# pcmcia.net
KiCad netlist of a schematic drawn in Altium Designer
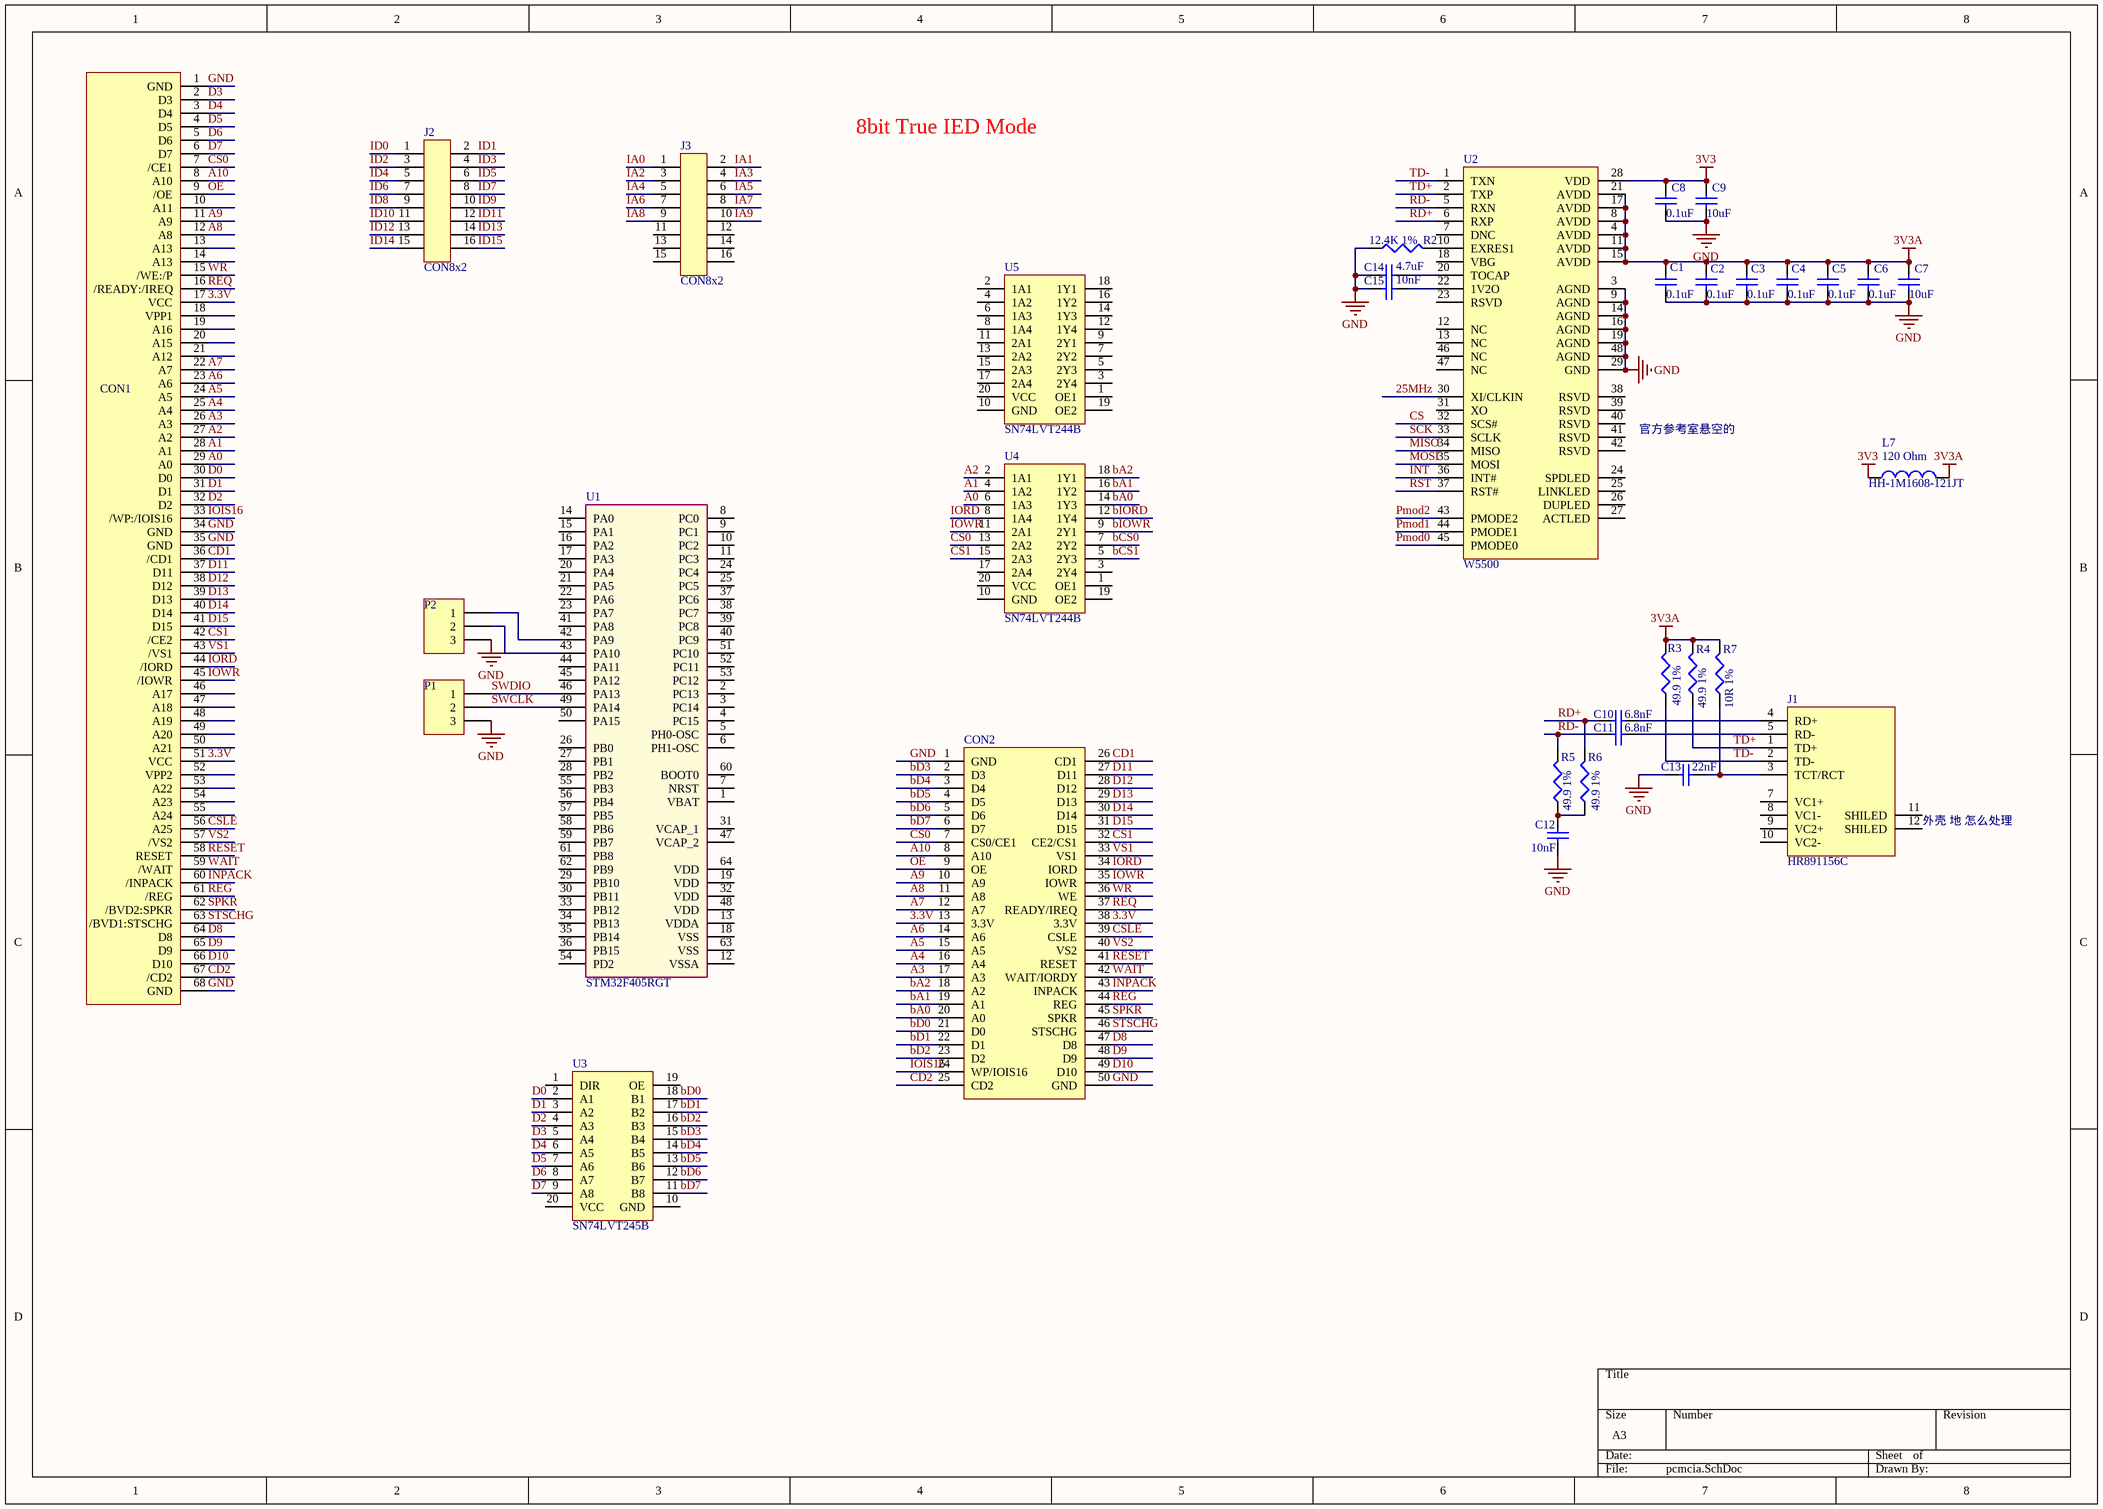
[diagram p0: pcmcia.SchDoc]

(export (version "E")
  (design (tool "Eeschema 10.0.6"))
  (components
    (comp (ref "C1")
      (value "0.1uF")
      (footprint "0603_C")
      (fields (field (name "PUBLISHER") "Altium Limited"))
      (libsource (lib "misc") (part "Cap"))
    )
    (comp (ref "C2")
      (value "0.1uF")
      (footprint "0603_C")
      (fields (field (name "PUBLISHER") "Altium Limited"))
      (libsource (lib "misc") (part "Cap"))
    )
    (comp (ref "C3")
      (value "0.1uF")
      (footprint "0603_C")
      (fields (field (name "PUBLISHER") "Altium Limited"))
      (libsource (lib "misc") (part "Cap"))
    )
    (comp (ref "C4")
      (value "0.1uF")
      (footprint "0603_C")
      (fields (field (name "PUBLISHER") "Altium Limited"))
      (libsource (lib "misc") (part "Cap"))
    )
    (comp (ref "C5")
      (value "0.1uF")
      (footprint "0603_C")
      (fields (field (name "PUBLISHER") "Altium Limited"))
      (libsource (lib "misc") (part "Cap"))
    )
    (comp (ref "C6")
      (value "0.1uF")
      (footprint "0603_C")
      (fields (field (name "PUBLISHER") "Altium Limited"))
      (libsource (lib "misc") (part "Cap"))
    )
    (comp (ref "C7")
      (value "10uF")
      (footprint "0603_C")
      (fields (field (name "PUBLISHER") "Altium Limited"))
      (libsource (lib "misc") (part "Cap"))
    )
    (comp (ref "C8")
      (value "0.1uF")
      (footprint "C0603")
      (fields (field (name "PUBLISHER") "Altium Limited"))
      (libsource (lib "misc") (part "Cap"))
    )
    (comp (ref "C9")
      (value "10uF")
      (footprint "C0603")
      (fields (field (name "PUBLISHER") "Altium Limited"))
      (libsource (lib "misc") (part "Cap"))
    )
    (comp (ref "C10")
      (value "6.8nF")
      (footprint "0603_C")
      (fields (field (name "PUBLISHER") "Altium Limited"))
      (libsource (lib "misc") (part "Cap"))
    )
    (comp (ref "C11")
      (value "6.8nF")
      (footprint "0603_C")
      (fields (field (name "PUBLISHER") "Altium Limited"))
      (libsource (lib "misc") (part "Cap"))
    )
    (comp (ref "C12")
      (value "10nF")
      (footprint "0603_C")
      (fields (field (name "PUBLISHER") "Altium Limited"))
      (libsource (lib "misc") (part "Cap"))
    )
    (comp (ref "C13")
      (value "22nF")
      (footprint "0603_C")
      (fields (field (name "PUBLISHER") "Altium Limited"))
      (libsource (lib "misc") (part "Cap"))
    )
    (comp (ref "C14")
      (value "4.7uF")
      (footprint "0603_C")
      (fields (field (name "PUBLISHER") "Altium Limited"))
      (libsource (lib "misc") (part "Cap"))
    )
    (comp (ref "C15")
      (value "10nF")
      (footprint "0603_C")
      (fields (field (name "PUBLISHER") "Altium Limited"))
      (libsource (lib "misc") (part "Cap"))
    )
    (comp (ref "CON1")
      (value "Ultrasonic")
      (footprint "PCMCIA_68pin_F")
      (libsource (lib "pcmcia") (part "Ultrasonic"))
    )
    (comp (ref "CON2") (value "AT89S52_1") (footprint "DIP40") (libsource (lib "pcmcia") (part "AT89S52_1")))
    (comp (ref "J1")
      (value "HR891156C")
      (footprint "HR891156C")
      (description "with POE")
      (libsource (lib "misc1") (part "HR891156C"))
    )
    (comp (ref "J2") (value "CON8x2") (footprint "CON8x2") (libsource (lib "misc") (part "CON8x2")))
    (comp (ref "J3") (value "CON8x2") (footprint "CON8x2") (libsource (lib "misc") (part "CON8x2")))
    (comp (ref "L7")
      (value "HH-1M1608-121JT")
      (footprint "L0805")
      (fields (field (name "ALTIUM_UNNAMED_1") "120 Ohm") (field (name "PUBLISHER") "Altium Limited"))
      (libsource (lib "misc") (part "Ind"))
    )
    (comp (ref "P1")
      (value "~")
      (footprint "CON3-SMT")
      (description "Header, 3-Pin")
      (fields (field (name "PUBLISHER") "Altium Limited"))
      (libsource (lib "Miscellaneous Connectors") (part "Header 3"))
    )
    (comp (ref "P2")
      (value "~")
      (footprint "CON3-SMT")
      (description "Header, 3-Pin")
      (fields (field (name "PUBLISHER") "Altium Limited"))
      (libsource (lib "Miscellaneous Connectors") (part "Header 3"))
    )
    (comp (ref "R2")
      (value "12.4K 1%")
      (footprint "0603_R")
      (fields (field (name "PUBLISHER") "Altium Limited"))
      (libsource (lib "misc") (part "Res"))
    )
    (comp (ref "R3")
      (value "49.9 1%")
      (footprint "0603_R")
      (fields (field (name "PUBLISHER") "Altium Limited"))
      (libsource (lib "misc") (part "Res"))
    )
    (comp (ref "R4")
      (value "49.9 1%")
      (footprint "0603_R")
      (fields (field (name "PUBLISHER") "Altium Limited"))
      (libsource (lib "misc") (part "Res"))
    )
    (comp (ref "R5")
      (value "49.9 1%")
      (footprint "0603_R")
      (fields (field (name "PUBLISHER") "Altium Limited"))
      (libsource (lib "misc") (part "Res"))
    )
    (comp (ref "R6")
      (value "49.9 1%")
      (footprint "0603_R")
      (fields (field (name "PUBLISHER") "Altium Limited"))
      (libsource (lib "misc") (part "Res"))
    )
    (comp (ref "R7")
      (value "10R 1%")
      (footprint "0603_R")
      (fields (field (name "PUBLISHER") "Altium Limited"))
      (libsource (lib "misc") (part "Res"))
    )
    (comp (ref "U1")
      (value "STM32F405RGT")
      (footprint "LQFP64-10x10")
      (libsource (lib "MCU") (part "STM32F405RGT"))
    )
    (comp (ref "U2") (value "W5500") (footprint "LQFP48-7x7") (libsource (lib "misc1") (part "W5500")))
    (comp (ref "U3") (value "SN74LVT245B") (libsource (lib "misc1") (part "SN74LVT245B")))
    (comp (ref "U4") (value "SN74LVT244B") (libsource (lib "misc1") (part "SN74LVT244B")))
    (comp (ref "U5") (value "SN74LVT244B") (libsource (lib "misc1") (part "SN74LVT244B")))
  )
  (nets
    (net (code "1") (name "/3.3V") (class "Default")
      (node (ref "CON1") (pin "17") (pinfunction "VCC_17") (pintype "passive"))
      (node (ref "CON1") (pin "51") (pinfunction "VCC_51") (pintype "passive"))
      (node (ref "CON2") (pin "13") (pinfunction "3.3V_13") (pintype "passive"))
      (node (ref "CON2") (pin "38") (pinfunction "3.3V_38") (pintype "passive"))
    )
    (net (code "2") (name "/25MHz") (class "Default")
      (node (ref "U2") (pin "30") (pinfunction "XI/CLKIN_30") (pintype "passive"))
    )
    (net (code "3") (name "/A0") (class "Default")
      (node (ref "CON1") (pin "29") (pinfunction "A0_29") (pintype "passive"))
      (node (ref "U4") (pin "6") (pinfunction "1A3_6") (pintype "passive"))
    )
    (net (code "4") (name "/A1") (class "Default")
      (node (ref "CON1") (pin "28") (pinfunction "A1_28") (pintype "passive"))
      (node (ref "U4") (pin "4") (pinfunction "1A2_4") (pintype "passive"))
    )
    (net (code "5") (name "/A2") (class "Default")
      (node (ref "CON1") (pin "27") (pinfunction "A2_27") (pintype "passive"))
      (node (ref "U4") (pin "2") (pinfunction "1A1_2") (pintype "passive"))
    )
    (net (code "6") (name "/A3") (class "Default")
      (node (ref "CON1") (pin "26") (pinfunction "A3_26") (pintype "passive"))
      (node (ref "CON2") (pin "17") (pinfunction "A3_17") (pintype "passive"))
    )
    (net (code "7") (name "/A4") (class "Default")
      (node (ref "CON1") (pin "25") (pinfunction "A4_25") (pintype "passive"))
      (node (ref "CON2") (pin "16") (pinfunction "A4_16") (pintype "passive"))
    )
    (net (code "8") (name "/A5") (class "Default")
      (node (ref "CON1") (pin "24") (pinfunction "A5_24") (pintype "passive"))
      (node (ref "CON2") (pin "15") (pinfunction "A5_15") (pintype "passive"))
    )
    (net (code "9") (name "/A6") (class "Default")
      (node (ref "CON1") (pin "23") (pinfunction "A6_23") (pintype "passive"))
      (node (ref "CON2") (pin "14") (pinfunction "A6_14") (pintype "passive"))
    )
    (net (code "10") (name "/A7") (class "Default")
      (node (ref "CON1") (pin "22") (pinfunction "A7_22") (pintype "passive"))
      (node (ref "CON2") (pin "12") (pinfunction "A7_12") (pintype "passive"))
    )
    (net (code "11") (name "/A8") (class "Default")
      (node (ref "CON1") (pin "12") (pinfunction "A8_12") (pintype "passive"))
      (node (ref "CON2") (pin "11") (pinfunction "A8_11") (pintype "passive"))
    )
    (net (code "12") (name "/A9") (class "Default")
      (node (ref "CON1") (pin "11") (pinfunction "A9_11") (pintype "passive"))
      (node (ref "CON2") (pin "10") (pinfunction "A9_10") (pintype "passive"))
    )
    (net (code "13") (name "/A10") (class "Default")
      (node (ref "CON1") (pin "8") (pinfunction "A10_8") (pintype "passive"))
      (node (ref "CON2") (pin "8") (pinfunction "A10_8") (pintype "passive"))
    )
    (net (code "14") (name "/CD1") (class "Default")
      (node (ref "CON1") (pin "36") (pinfunction "/CD1_36") (pintype "passive"))
      (node (ref "CON2") (pin "26") (pinfunction "CD1_26") (pintype "passive"))
    )
    (net (code "15") (name "/CD2") (class "Default")
      (node (ref "CON1") (pin "67") (pinfunction "/CD2_67") (pintype "passive"))
      (node (ref "CON2") (pin "25") (pinfunction "CD2_25") (pintype "passive"))
    )
    (net (code "16") (name "/CS") (class "Default")
      (node (ref "U2") (pin "32") (pinfunction "SCS#_32") (pintype "passive"))
    )
    (net (code "17") (name "/CS0") (class "Default")
      (node (ref "CON1") (pin "7") (pinfunction "/CE1_7") (pintype "passive"))
      (node (ref "CON2") (pin "7") (pinfunction "CS0/CE1_7") (pintype "passive"))
      (node (ref "U4") (pin "13") (pinfunction "2A2_13") (pintype "passive"))
    )
    (net (code "18") (name "/CS1") (class "Default")
      (node (ref "CON1") (pin "42") (pinfunction "/CE2_42") (pintype "passive"))
      (node (ref "CON2") (pin "32") (pinfunction "CE2/CS1_32") (pintype "passive"))
      (node (ref "U4") (pin "15") (pinfunction "2A3_15") (pintype "passive"))
    )
    (net (code "19") (name "/CSLE") (class "Default")
      (node (ref "CON1") (pin "56") (pinfunction "A25_56") (pintype "passive"))
      (node (ref "CON2") (pin "39") (pinfunction "CSLE_39") (pintype "passive"))
    )
    (net (code "20") (name "/D0") (class "Default")
      (node (ref "CON1") (pin "30") (pinfunction "D0_30") (pintype "passive"))
      (node (ref "U3") (pin "2") (pinfunction "A1_2") (pintype "passive"))
    )
    (net (code "21") (name "/D1") (class "Default")
      (node (ref "CON1") (pin "31") (pinfunction "D1_31") (pintype "passive"))
      (node (ref "U3") (pin "3") (pinfunction "A2_3") (pintype "passive"))
    )
    (net (code "22") (name "/D2") (class "Default")
      (node (ref "CON1") (pin "32") (pinfunction "D2_32") (pintype "passive"))
      (node (ref "U3") (pin "4") (pinfunction "A3_4") (pintype "passive"))
    )
    (net (code "23") (name "/D3") (class "Default")
      (node (ref "CON1") (pin "2") (pinfunction "D3_2") (pintype "passive"))
      (node (ref "U3") (pin "5") (pinfunction "A4_5") (pintype "passive"))
    )
    (net (code "24") (name "/D4") (class "Default")
      (node (ref "CON1") (pin "3") (pinfunction "D4_3") (pintype "passive"))
      (node (ref "U3") (pin "6") (pinfunction "A5_6") (pintype "passive"))
    )
    (net (code "25") (name "/D5") (class "Default")
      (node (ref "CON1") (pin "4") (pinfunction "D5_4") (pintype "passive"))
      (node (ref "U3") (pin "7") (pinfunction "A6_7") (pintype "passive"))
    )
    (net (code "26") (name "/D6") (class "Default")
      (node (ref "CON1") (pin "5") (pinfunction "D6_5") (pintype "passive"))
      (node (ref "U3") (pin "8") (pinfunction "A7_8") (pintype "passive"))
    )
    (net (code "27") (name "/D7") (class "Default")
      (node (ref "CON1") (pin "6") (pinfunction "D7_6") (pintype "passive"))
      (node (ref "U3") (pin "9") (pinfunction "A8_9") (pintype "passive"))
    )
    (net (code "28") (name "/D8") (class "Default")
      (node (ref "CON1") (pin "64") (pinfunction "D8_64") (pintype "passive"))
      (node (ref "CON2") (pin "47") (pinfunction "D8_47") (pintype "passive"))
    )
    (net (code "29") (name "/D9") (class "Default")
      (node (ref "CON1") (pin "65") (pinfunction "D9_65") (pintype "passive"))
      (node (ref "CON2") (pin "48") (pinfunction "D9_48") (pintype "passive"))
    )
    (net (code "30") (name "/D10") (class "Default")
      (node (ref "CON1") (pin "66") (pinfunction "D10_66") (pintype "passive"))
      (node (ref "CON2") (pin "49") (pinfunction "D10_49") (pintype "passive"))
    )
    (net (code "31") (name "/D11") (class "Default")
      (node (ref "CON1") (pin "37") (pinfunction "D11_37") (pintype "passive"))
      (node (ref "CON2") (pin "27") (pinfunction "D11_27") (pintype "passive"))
    )
    (net (code "32") (name "/D12") (class "Default")
      (node (ref "CON1") (pin "38") (pinfunction "D12_38") (pintype "passive"))
      (node (ref "CON2") (pin "28") (pinfunction "D12_28") (pintype "passive"))
    )
    (net (code "33") (name "/D13") (class "Default")
      (node (ref "CON1") (pin "39") (pinfunction "D13_39") (pintype "passive"))
      (node (ref "CON2") (pin "29") (pinfunction "D13_29") (pintype "passive"))
    )
    (net (code "34") (name "/D14") (class "Default")
      (node (ref "CON1") (pin "40") (pinfunction "D14_40") (pintype "passive"))
      (node (ref "CON2") (pin "30") (pinfunction "D14_30") (pintype "passive"))
    )
    (net (code "35") (name "/D15") (class "Default")
      (node (ref "CON1") (pin "41") (pinfunction "D15_41") (pintype "passive"))
      (node (ref "CON2") (pin "31") (pinfunction "D15_31") (pintype "passive"))
    )
    (net (code "36") (name "/IA0") (class "Default") (node (ref "J3") (pin "1") (pintype "passive")))
    (net (code "37") (name "/IA1") (class "Default") (node (ref "J3") (pin "2") (pintype "passive")))
    (net (code "38") (name "/IA2") (class "Default") (node (ref "J3") (pin "3") (pintype "passive")))
    (net (code "39") (name "/IA3") (class "Default") (node (ref "J3") (pin "4") (pintype "passive")))
    (net (code "40") (name "/IA4") (class "Default") (node (ref "J3") (pin "5") (pintype "passive")))
    (net (code "41") (name "/IA5") (class "Default") (node (ref "J3") (pin "6") (pintype "passive")))
    (net (code "42") (name "/IA6") (class "Default") (node (ref "J3") (pin "7") (pintype "passive")))
    (net (code "43") (name "/IA7") (class "Default") (node (ref "J3") (pin "8") (pintype "passive")))
    (net (code "44") (name "/IA8") (class "Default") (node (ref "J3") (pin "9") (pintype "passive")))
    (net (code "45") (name "/IA9") (class "Default") (node (ref "J3") (pin "10") (pintype "passive")))
    (net (code "46") (name "/ID0") (class "Default") (node (ref "J2") (pin "1") (pintype "passive")))
    (net (code "47") (name "/ID1") (class "Default") (node (ref "J2") (pin "2") (pintype "passive")))
    (net (code "48") (name "/ID2") (class "Default") (node (ref "J2") (pin "3") (pintype "passive")))
    (net (code "49") (name "/ID3") (class "Default") (node (ref "J2") (pin "4") (pintype "passive")))
    (net (code "50") (name "/ID4") (class "Default") (node (ref "J2") (pin "5") (pintype "passive")))
    (net (code "51") (name "/ID5") (class "Default") (node (ref "J2") (pin "6") (pintype "passive")))
    (net (code "52") (name "/ID6") (class "Default") (node (ref "J2") (pin "7") (pintype "passive")))
    (net (code "53") (name "/ID7") (class "Default") (node (ref "J2") (pin "8") (pintype "passive")))
    (net (code "54") (name "/ID8") (class "Default") (node (ref "J2") (pin "9") (pintype "passive")))
    (net (code "55") (name "/ID9") (class "Default") (node (ref "J2") (pin "10") (pintype "passive")))
    (net (code "56") (name "/ID10") (class "Default") (node (ref "J2") (pin "11") (pintype "passive")))
    (net (code "57") (name "/ID11") (class "Default") (node (ref "J2") (pin "12") (pintype "passive")))
    (net (code "58") (name "/ID12") (class "Default") (node (ref "J2") (pin "13") (pintype "passive")))
    (net (code "59") (name "/ID13") (class "Default") (node (ref "J2") (pin "14") (pintype "passive")))
    (net (code "60") (name "/ID14") (class "Default") (node (ref "J2") (pin "15") (pintype "passive")))
    (net (code "61") (name "/ID15") (class "Default") (node (ref "J2") (pin "16") (pintype "passive")))
    (net (code "62") (name "/INPACK") (class "Default")
      (node (ref "CON1") (pin "60") (pinfunction "/INPACK_60") (pintype "passive"))
      (node (ref "CON2") (pin "43") (pinfunction "INPACK_43") (pintype "passive"))
    )
    (net (code "63") (name "/INT") (class "Default")
      (node (ref "U2") (pin "36") (pinfunction "INT#_36") (pintype "passive"))
    )
    (net (code "64") (name "/IOIS16") (class "Default")
      (node (ref "CON1") (pin "33") (pinfunction "/WP:/IOIS16_33") (pintype "passive"))
      (node (ref "CON2") (pin "24") (pinfunction "WP/IOIS16_24") (pintype "passive"))
    )
    (net (code "65") (name "/IORD") (class "Default")
      (node (ref "CON1") (pin "44") (pinfunction "/IORD_44") (pintype "passive"))
      (node (ref "CON2") (pin "34") (pinfunction "IORD_34") (pintype "passive"))
      (node (ref "U4") (pin "8") (pinfunction "1A4_8") (pintype "passive"))
    )
    (net (code "66") (name "/IOWR") (class "Default")
      (node (ref "CON1") (pin "45") (pinfunction "/IOWR_45") (pintype "passive"))
      (node (ref "CON2") (pin "35") (pinfunction "IOWR_35") (pintype "passive"))
      (node (ref "U4") (pin "11") (pinfunction "2A1_11") (pintype "passive"))
    )
    (net (code "67") (name "/MISO") (class "Default")
      (node (ref "U2") (pin "34") (pinfunction "MISO_34") (pintype "passive"))
    )
    (net (code "68") (name "/MOSI") (class "Default")
      (node (ref "U2") (pin "35") (pinfunction "MOSI_35") (pintype "passive"))
    )
    (net (code "69") (name "/OE") (class "Default")
      (node (ref "CON1") (pin "9") (pinfunction "/OE_9") (pintype "passive"))
      (node (ref "CON2") (pin "9") (pinfunction "OE_9") (pintype "passive"))
    )
    (net (code "70") (name "/Pmod0") (class "Default")
      (node (ref "U2") (pin "45") (pinfunction "PMODE0_45") (pintype "passive"))
    )
    (net (code "71") (name "/Pmod1") (class "Default")
      (node (ref "U2") (pin "44") (pinfunction "PMODE1_44") (pintype "passive"))
    )
    (net (code "72") (name "/Pmod2") (class "Default")
      (node (ref "U2") (pin "43") (pinfunction "PMODE2_43") (pintype "passive"))
    )
    (net (code "73") (name "/RD+") (class "Default")
      (node (ref "C10") (pin "2") (pinfunction "2_2") (pintype "passive"))
      (node (ref "R6") (pin "2") (pinfunction "2_2") (pintype "passive"))
      (node (ref "U2") (pin "6") (pinfunction "RXP_6") (pintype "passive"))
    )
    (net (code "74") (name "/RD-") (class "Default")
      (node (ref "C11") (pin "2") (pinfunction "2_2") (pintype "passive"))
      (node (ref "R5") (pin "2") (pinfunction "2_2") (pintype "passive"))
      (node (ref "U2") (pin "5") (pinfunction "RXN_5") (pintype "passive"))
    )
    (net (code "75") (name "/REG") (class "Default")
      (node (ref "CON1") (pin "61") (pinfunction "/REG_61") (pintype "passive"))
      (node (ref "CON2") (pin "44") (pinfunction "REG_44") (pintype "passive"))
    )
    (net (code "76") (name "/REQ") (class "Default")
      (node (ref "CON1") (pin "16") (pinfunction "/READY:/IREQ_16") (pintype "passive"))
      (node (ref "CON2") (pin "37") (pinfunction "READY/IREQ_37") (pintype "passive"))
    )
    (net (code "77") (name "/RESET") (class "Default")
      (node (ref "CON1") (pin "58") (pinfunction "RESET_58") (pintype "passive"))
      (node (ref "CON2") (pin "41") (pinfunction "RESET_41") (pintype "passive"))
    )
    (net (code "78") (name "/RST") (class "Default")
      (node (ref "U2") (pin "37") (pinfunction "RST#_37") (pintype "passive"))
    )
    (net (code "79") (name "/SCK") (class "Default")
      (node (ref "U2") (pin "33") (pinfunction "SCLK_33") (pintype "passive"))
    )
    (net (code "80") (name "/SPKR") (class "Default")
      (node (ref "CON1") (pin "62") (pinfunction "/BVD2:SPKR_62") (pintype "passive"))
      (node (ref "CON2") (pin "45") (pinfunction "SPKR_45") (pintype "passive"))
    )
    (net (code "81") (name "/STSCHG") (class "Default")
      (node (ref "CON1") (pin "63") (pinfunction "/BVD1:STSCHG_63") (pintype "passive"))
      (node (ref "CON2") (pin "46") (pinfunction "STSCHG_46") (pintype "passive"))
    )
    (net (code "82") (name "/SWCLK") (class "Default")
      (node (ref "P1") (pin "2") (pinfunction "2_2") (pintype "passive"))
      (node (ref "U1") (pin "49") (pinfunction "PA14_49") (pintype "passive"))
    )
    (net (code "83") (name "/SWDIO") (class "Default")
      (node (ref "P1") (pin "1") (pinfunction "1_1") (pintype "passive"))
      (node (ref "U1") (pin "46") (pinfunction "PA13_46") (pintype "passive"))
    )
    (net (code "84") (name "/TD+") (class "Default")
      (node (ref "J1") (pin "1") (pinfunction "TD+_1") (pintype "passive"))
      (node (ref "R4") (pin "1") (pinfunction "1_1") (pintype "passive"))
      (node (ref "U2") (pin "2") (pinfunction "TXP_2") (pintype "passive"))
    )
    (net (code "85") (name "/TD-") (class "Default")
      (node (ref "J1") (pin "2") (pinfunction "TD-_2") (pintype "passive"))
      (node (ref "R3") (pin "1") (pinfunction "1_1") (pintype "passive"))
      (node (ref "U2") (pin "1") (pinfunction "TXN_1") (pintype "passive"))
    )
    (net (code "86") (name "/VS1") (class "Default")
      (node (ref "CON1") (pin "43") (pinfunction "/VS1_43") (pintype "passive"))
      (node (ref "CON2") (pin "33") (pinfunction "VS1_33") (pintype "passive"))
    )
    (net (code "87") (name "/VS2") (class "Default")
      (node (ref "CON1") (pin "57") (pinfunction "/VS2_57") (pintype "passive"))
      (node (ref "CON2") (pin "40") (pinfunction "VS2_40") (pintype "passive"))
    )
    (net (code "88") (name "/WAIT") (class "Default")
      (node (ref "CON1") (pin "59") (pinfunction "/WAIT_59") (pintype "passive"))
      (node (ref "CON2") (pin "42") (pinfunction "WAIT/IORDY_42") (pintype "passive"))
    )
    (net (code "89") (name "/WR") (class "Default")
      (node (ref "CON1") (pin "15") (pinfunction "/WE:/P_15") (pintype "passive"))
      (node (ref "CON2") (pin "36") (pinfunction "WE_36") (pintype "passive"))
    )
    (net (code "90") (name "/bA0") (class "Default")
      (node (ref "CON2") (pin "20") (pinfunction "A0_20") (pintype "passive"))
      (node (ref "U4") (pin "14") (pinfunction "1Y3_14") (pintype "passive"))
    )
    (net (code "91") (name "/bA1") (class "Default")
      (node (ref "CON2") (pin "19") (pinfunction "A1_19") (pintype "passive"))
      (node (ref "U4") (pin "16") (pinfunction "1Y2_16") (pintype "passive"))
    )
    (net (code "92") (name "/bA2") (class "Default")
      (node (ref "CON2") (pin "18") (pinfunction "A2_18") (pintype "passive"))
      (node (ref "U4") (pin "18") (pinfunction "1Y1_18") (pintype "passive"))
    )
    (net (code "93") (name "/bCS0") (class "Default")
      (node (ref "U4") (pin "7") (pinfunction "2Y2_7") (pintype "passive"))
    )
    (net (code "94") (name "/bCS1") (class "Default")
      (node (ref "U4") (pin "5") (pinfunction "2Y3_5") (pintype "passive"))
    )
    (net (code "95") (name "/bD0") (class "Default")
      (node (ref "CON2") (pin "21") (pinfunction "D0_21") (pintype "passive"))
      (node (ref "U3") (pin "18") (pinfunction "B1_18") (pintype "passive"))
    )
    (net (code "96") (name "/bD1") (class "Default")
      (node (ref "CON2") (pin "22") (pinfunction "D1_22") (pintype "passive"))
      (node (ref "U3") (pin "17") (pinfunction "B2_17") (pintype "passive"))
    )
    (net (code "97") (name "/bD2") (class "Default")
      (node (ref "CON2") (pin "23") (pinfunction "D2_23") (pintype "passive"))
      (node (ref "U3") (pin "16") (pinfunction "B3_16") (pintype "passive"))
    )
    (net (code "98") (name "/bD3") (class "Default")
      (node (ref "CON2") (pin "2") (pinfunction "D3_2") (pintype "passive"))
      (node (ref "U3") (pin "15") (pinfunction "B4_15") (pintype "passive"))
    )
    (net (code "99") (name "/bD4") (class "Default")
      (node (ref "CON2") (pin "3") (pinfunction "D4_3") (pintype "passive"))
      (node (ref "U3") (pin "14") (pinfunction "B5_14") (pintype "passive"))
    )
    (net (code "100") (name "/bD5") (class "Default")
      (node (ref "CON2") (pin "4") (pinfunction "D5_4") (pintype "passive"))
      (node (ref "U3") (pin "13") (pinfunction "B6_13") (pintype "passive"))
    )
    (net (code "101") (name "/bD6") (class "Default")
      (node (ref "CON2") (pin "5") (pinfunction "D6_5") (pintype "passive"))
      (node (ref "U3") (pin "12") (pinfunction "B7_12") (pintype "passive"))
    )
    (net (code "102") (name "/bD7") (class "Default")
      (node (ref "CON2") (pin "6") (pinfunction "D7_6") (pintype "passive"))
      (node (ref "U3") (pin "11") (pinfunction "B8_11") (pintype "passive"))
    )
    (net (code "103") (name "/bIORD") (class "Default")
      (node (ref "U4") (pin "12") (pinfunction "1Y4_12") (pintype "passive"))
    )
    (net (code "104") (name "/bIOWR") (class "Default")
      (node (ref "U4") (pin "9") (pinfunction "2Y1_9") (pintype "passive"))
    )
    (net (code "105") (name "3V3") (class "Default")
      (node (ref "C8") (pin "2") (pinfunction "2_2") (pintype "passive"))
      (node (ref "C9") (pin "2") (pinfunction "2_2") (pintype "passive"))
      (node (ref "L7") (pin "1") (pinfunction "1_1") (pintype "passive"))
      (node (ref "U2") (pin "28") (pinfunction "VDD_28") (pintype "passive"))
    )
    (net (code "106") (name "3V3A") (class "Default")
      (node (ref "C1") (pin "2") (pinfunction "2_2") (pintype "passive"))
      (node (ref "C2") (pin "2") (pinfunction "2_2") (pintype "passive"))
      (node (ref "C3") (pin "2") (pinfunction "2_2") (pintype "passive"))
      (node (ref "C4") (pin "2") (pinfunction "2_2") (pintype "passive"))
      (node (ref "C5") (pin "2") (pinfunction "2_2") (pintype "passive"))
      (node (ref "C6") (pin "2") (pinfunction "2_2") (pintype "passive"))
      (node (ref "C7") (pin "2") (pinfunction "2_2") (pintype "passive"))
      (node (ref "L7") (pin "2") (pinfunction "2_2") (pintype "passive"))
      (node (ref "R3") (pin "2") (pinfunction "2_2") (pintype "passive"))
      (node (ref "R4") (pin "2") (pinfunction "2_2") (pintype "passive"))
      (node (ref "R7") (pin "2") (pinfunction "2_2") (pintype "passive"))
      (node (ref "U2") (pin "11") (pinfunction "AVDD_11") (pintype "passive"))
      (node (ref "U2") (pin "15") (pinfunction "AVDD_15") (pintype "passive"))
      (node (ref "U2") (pin "17") (pinfunction "AVDD_17") (pintype "passive"))
      (node (ref "U2") (pin "21") (pinfunction "AVDD_21") (pintype "passive"))
      (node (ref "U2") (pin "4") (pinfunction "AVDD_4") (pintype "passive"))
      (node (ref "U2") (pin "8") (pinfunction "AVDD_8") (pintype "passive"))
    )
    (net (code "107") (name "GND") (class "Default")
      (node (ref "C1") (pin "1") (pinfunction "1_1") (pintype "passive"))
      (node (ref "C12") (pin "2") (pinfunction "2_2") (pintype "passive"))
      (node (ref "C13") (pin "1") (pinfunction "1_1") (pintype "passive"))
      (node (ref "C14") (pin "2") (pinfunction "2_2") (pintype "passive"))
      (node (ref "C15") (pin "2") (pinfunction "2_2") (pintype "passive"))
      (node (ref "C2") (pin "1") (pinfunction "1_1") (pintype "passive"))
      (node (ref "C3") (pin "1") (pinfunction "1_1") (pintype "passive"))
      (node (ref "C4") (pin "1") (pinfunction "1_1") (pintype "passive"))
      (node (ref "C5") (pin "1") (pinfunction "1_1") (pintype "passive"))
      (node (ref "C6") (pin "1") (pinfunction "1_1") (pintype "passive"))
      (node (ref "C7") (pin "1") (pinfunction "1_1") (pintype "passive"))
      (node (ref "C8") (pin "1") (pinfunction "1_1") (pintype "passive"))
      (node (ref "C9") (pin "1") (pinfunction "1_1") (pintype "passive"))
      (node (ref "CON1") (pin "1") (pinfunction "GND_1") (pintype "passive"))
      (node (ref "CON1") (pin "34") (pinfunction "GND_34") (pintype "passive"))
      (node (ref "CON1") (pin "35") (pinfunction "GND_35") (pintype "passive"))
      (node (ref "CON1") (pin "68") (pinfunction "GND_68") (pintype "passive"))
      (node (ref "CON2") (pin "1") (pinfunction "GND_1") (pintype "passive"))
      (node (ref "CON2") (pin "50") (pinfunction "GND_50") (pintype "passive"))
      (node (ref "P1") (pin "3") (pinfunction "3_3") (pintype "passive"))
      (node (ref "P2") (pin "3") (pinfunction "3_3") (pintype "passive"))
      (node (ref "R2") (pin "1") (pinfunction "1_1") (pintype "passive"))
      (node (ref "U2") (pin "14") (pinfunction "AGND_14") (pintype "passive"))
      (node (ref "U2") (pin "16") (pinfunction "AGND_16") (pintype "passive"))
      (node (ref "U2") (pin "19") (pinfunction "AGND_19") (pintype "passive"))
      (node (ref "U2") (pin "29") (pinfunction "GND_29") (pintype "passive"))
      (node (ref "U2") (pin "3") (pinfunction "AGND_3") (pintype "passive"))
      (node (ref "U2") (pin "48") (pinfunction "AGND_48") (pintype "passive"))
      (node (ref "U2") (pin "9") (pinfunction "AGND_9") (pintype "passive"))
    )
    (net (code "108") (name "Net-(C12-Pad1)") (class "Default")
      (node (ref "C12") (pin "1") (pinfunction "1_1") (pintype "passive"))
      (node (ref "R5") (pin "1") (pinfunction "1_1") (pintype "passive"))
      (node (ref "R6") (pin "1") (pinfunction "1_1") (pintype "passive"))
    )
    (net (code "109") (name "Net-(J1-RD+)") (class "Default")
      (node (ref "C10") (pin "1") (pinfunction "1_1") (pintype "passive"))
      (node (ref "J1") (pin "4") (pinfunction "RD+_4") (pintype "passive"))
    )
    (net (code "110") (name "Net-(J1-RD-)") (class "Default")
      (node (ref "C11") (pin "1") (pinfunction "1_1") (pintype "passive"))
      (node (ref "J1") (pin "5") (pinfunction "RD-_5") (pintype "passive"))
    )
    (net (code "111") (name "Net-(J1-TCT{slash}RCT)") (class "Default")
      (node (ref "C13") (pin "2") (pinfunction "2_2") (pintype "passive"))
      (node (ref "J1") (pin "3") (pinfunction "TCT/RCT_3") (pintype "passive"))
      (node (ref "R7") (pin "1") (pinfunction "1_1") (pintype "passive"))
    )
    (net (code "112") (name "Net-(U1-PA9)") (class "Default")
      (node (ref "P2") (pin "1") (pinfunction "1_1") (pintype "passive"))
      (node (ref "U1") (pin "42") (pinfunction "PA9_42") (pintype "passive"))
    )
    (net (code "113") (name "Net-(U1-PA10)") (class "Default")
      (node (ref "P2") (pin "2") (pinfunction "2_2") (pintype "passive"))
      (node (ref "U1") (pin "43") (pinfunction "PA10_43") (pintype "passive"))
    )
    (net (code "114") (name "Net-(U2-1V2O)") (class "Default")
      (node (ref "C15") (pin "1") (pinfunction "1_1") (pintype "passive"))
      (node (ref "U2") (pin "22") (pinfunction "1V2O_22") (pintype "passive"))
    )
    (net (code "115") (name "Net-(U2-EXRES1)") (class "Default")
      (node (ref "R2") (pin "2") (pinfunction "2_2") (pintype "passive"))
      (node (ref "U2") (pin "10") (pinfunction "EXRES1_10") (pintype "passive"))
    )
    (net (code "116") (name "Net-(U2-TOCAP)") (class "Default")
      (node (ref "C14") (pin "1") (pinfunction "1_1") (pintype "passive"))
      (node (ref "U2") (pin "20") (pinfunction "TOCAP_20") (pintype "passive"))
    )
    (net (code "117") (name "unconnected-(CON1-A11-Pad10)") (class "Default")
      (node (ref "CON1") (pin "10") (pinfunction "A11_10") (pintype "passive"))
    )
    (net (code "118") (name "unconnected-(CON1-A12-Pad21)") (class "Default")
      (node (ref "CON1") (pin "21") (pinfunction "A12_21") (pintype "passive"))
    )
    (net (code "119") (name "unconnected-(CON1-A13-Pad13)") (class "Default")
      (node (ref "CON1") (pin "13") (pinfunction "A13_13") (pintype "passive"))
    )
    (net (code "120") (name "unconnected-(CON1-A13-Pad14)") (class "Default")
      (node (ref "CON1") (pin "14") (pinfunction "A13_14") (pintype "passive"))
    )
    (net (code "121") (name "unconnected-(CON1-A15-Pad20)") (class "Default")
      (node (ref "CON1") (pin "20") (pinfunction "A15_20") (pintype "passive"))
    )
    (net (code "122") (name "unconnected-(CON1-A16-Pad19)") (class "Default")
      (node (ref "CON1") (pin "19") (pinfunction "A16_19") (pintype "passive"))
    )
    (net (code "123") (name "unconnected-(CON1-A17-Pad46)") (class "Default")
      (node (ref "CON1") (pin "46") (pinfunction "A17_46") (pintype "passive"))
    )
    (net (code "124") (name "unconnected-(CON1-A18-Pad47)") (class "Default")
      (node (ref "CON1") (pin "47") (pinfunction "A18_47") (pintype "passive"))
    )
    (net (code "125") (name "unconnected-(CON1-A19-Pad48)") (class "Default")
      (node (ref "CON1") (pin "48") (pinfunction "A19_48") (pintype "passive"))
    )
    (net (code "126") (name "unconnected-(CON1-A20-Pad49)") (class "Default")
      (node (ref "CON1") (pin "49") (pinfunction "A20_49") (pintype "passive"))
    )
    (net (code "127") (name "unconnected-(CON1-A21-Pad50)") (class "Default")
      (node (ref "CON1") (pin "50") (pinfunction "A21_50") (pintype "passive"))
    )
    (net (code "128") (name "unconnected-(CON1-A22-Pad53)") (class "Default")
      (node (ref "CON1") (pin "53") (pinfunction "A22_53") (pintype "passive"))
    )
    (net (code "129") (name "unconnected-(CON1-A23-Pad54)") (class "Default")
      (node (ref "CON1") (pin "54") (pinfunction "A23_54") (pintype "passive"))
    )
    (net (code "130") (name "unconnected-(CON1-A24-Pad55)") (class "Default")
      (node (ref "CON1") (pin "55") (pinfunction "A24_55") (pintype "passive"))
    )
    (net (code "131") (name "unconnected-(CON1-VPP1-Pad18)") (class "Default")
      (node (ref "CON1") (pin "18") (pinfunction "VPP1_18") (pintype "passive"))
    )
    (net (code "132") (name "unconnected-(CON1-VPP2-Pad52)") (class "Default")
      (node (ref "CON1") (pin "52") (pinfunction "VPP2_52") (pintype "passive"))
    )
    (net (code "133") (name "unconnected-(J1-SHILED-Pad11)") (class "Default")
      (node (ref "J1") (pin "11") (pinfunction "SHILED_11") (pintype "passive"))
    )
    (net (code "134") (name "unconnected-(J1-SHILED-Pad12)") (class "Default")
      (node (ref "J1") (pin "12") (pinfunction "SHILED_12") (pintype "passive"))
    )
    (net (code "135") (name "unconnected-(J1-VC1+-Pad7)") (class "Default")
      (node (ref "J1") (pin "7") (pinfunction "VC1+_7") (pintype "passive"))
    )
    (net (code "136") (name "unconnected-(J1-VC1--Pad8)") (class "Default")
      (node (ref "J1") (pin "8") (pinfunction "VC1-_8") (pintype "passive"))
    )
    (net (code "137") (name "unconnected-(J1-VC2+-Pad9)") (class "Default")
      (node (ref "J1") (pin "9") (pinfunction "VC2+_9") (pintype "passive"))
    )
    (net (code "138") (name "unconnected-(J1-VC2--Pad10)") (class "Default")
      (node (ref "J1") (pin "10") (pinfunction "VC2-_10") (pintype "passive"))
    )
    (net (code "139") (name "unconnected-(J3-Pad11)") (class "Default")
      (node (ref "J3") (pin "11") (pintype "passive"))
    )
    (net (code "140") (name "unconnected-(J3-Pad12)") (class "Default")
      (node (ref "J3") (pin "12") (pintype "passive"))
    )
    (net (code "141") (name "unconnected-(J3-Pad13)") (class "Default")
      (node (ref "J3") (pin "13") (pintype "passive"))
    )
    (net (code "142") (name "unconnected-(J3-Pad14)") (class "Default")
      (node (ref "J3") (pin "14") (pintype "passive"))
    )
    (net (code "143") (name "unconnected-(J3-Pad15)") (class "Default")
      (node (ref "J3") (pin "15") (pintype "passive"))
    )
    (net (code "144") (name "unconnected-(J3-Pad16)") (class "Default")
      (node (ref "J3") (pin "16") (pintype "passive"))
    )
    (net (code "145") (name "unconnected-(U1-BOOT0-Pad60)") (class "Default")
      (node (ref "U1") (pin "60") (pinfunction "BOOT0_60") (pintype "passive"))
    )
    (net (code "146") (name "unconnected-(U1-NRST-Pad7)") (class "Default")
      (node (ref "U1") (pin "7") (pinfunction "NRST_7") (pintype "passive"))
    )
    (net (code "147") (name "unconnected-(U1-PA0-Pad14)") (class "Default")
      (node (ref "U1") (pin "14") (pinfunction "PA0_14") (pintype "passive"))
    )
    (net (code "148") (name "unconnected-(U1-PA1-Pad15)") (class "Default")
      (node (ref "U1") (pin "15") (pinfunction "PA1_15") (pintype "passive"))
    )
    (net (code "149") (name "unconnected-(U1-PA2-Pad16)") (class "Default")
      (node (ref "U1") (pin "16") (pinfunction "PA2_16") (pintype "passive"))
    )
    (net (code "150") (name "unconnected-(U1-PA3-Pad17)") (class "Default")
      (node (ref "U1") (pin "17") (pinfunction "PA3_17") (pintype "passive"))
    )
    (net (code "151") (name "unconnected-(U1-PA4-Pad20)") (class "Default")
      (node (ref "U1") (pin "20") (pinfunction "PA4_20") (pintype "passive"))
    )
    (net (code "152") (name "unconnected-(U1-PA5-Pad21)") (class "Default")
      (node (ref "U1") (pin "21") (pinfunction "PA5_21") (pintype "passive"))
    )
    (net (code "153") (name "unconnected-(U1-PA6-Pad22)") (class "Default")
      (node (ref "U1") (pin "22") (pinfunction "PA6_22") (pintype "passive"))
    )
    (net (code "154") (name "unconnected-(U1-PA7-Pad23)") (class "Default")
      (node (ref "U1") (pin "23") (pinfunction "PA7_23") (pintype "passive"))
    )
    (net (code "155") (name "unconnected-(U1-PA8-Pad41)") (class "Default")
      (node (ref "U1") (pin "41") (pinfunction "PA8_41") (pintype "passive"))
    )
    (net (code "156") (name "unconnected-(U1-PA11-Pad44)") (class "Default")
      (node (ref "U1") (pin "44") (pinfunction "PA11_44") (pintype "passive"))
    )
    (net (code "157") (name "unconnected-(U1-PA12-Pad45)") (class "Default")
      (node (ref "U1") (pin "45") (pinfunction "PA12_45") (pintype "passive"))
    )
    (net (code "158") (name "unconnected-(U1-PA15-Pad50)") (class "Default")
      (node (ref "U1") (pin "50") (pinfunction "PA15_50") (pintype "passive"))
    )
    (net (code "159") (name "unconnected-(U1-PB0-Pad26)") (class "Default")
      (node (ref "U1") (pin "26") (pinfunction "PB0_26") (pintype "passive"))
    )
    (net (code "160") (name "unconnected-(U1-PB1-Pad27)") (class "Default")
      (node (ref "U1") (pin "27") (pinfunction "PB1_27") (pintype "passive"))
    )
    (net (code "161") (name "unconnected-(U1-PB2-Pad28)") (class "Default")
      (node (ref "U1") (pin "28") (pinfunction "PB2_28") (pintype "passive"))
    )
    (net (code "162") (name "unconnected-(U1-PB3-Pad55)") (class "Default")
      (node (ref "U1") (pin "55") (pinfunction "PB3_55") (pintype "passive"))
    )
    (net (code "163") (name "unconnected-(U1-PB4-Pad56)") (class "Default")
      (node (ref "U1") (pin "56") (pinfunction "PB4_56") (pintype "passive"))
    )
    (net (code "164") (name "unconnected-(U1-PB5-Pad57)") (class "Default")
      (node (ref "U1") (pin "57") (pinfunction "PB5_57") (pintype "passive"))
    )
    (net (code "165") (name "unconnected-(U1-PB6-Pad58)") (class "Default")
      (node (ref "U1") (pin "58") (pinfunction "PB6_58") (pintype "passive"))
    )
    (net (code "166") (name "unconnected-(U1-PB7-Pad59)") (class "Default")
      (node (ref "U1") (pin "59") (pinfunction "PB7_59") (pintype "passive"))
    )
    (net (code "167") (name "unconnected-(U1-PB8-Pad61)") (class "Default")
      (node (ref "U1") (pin "61") (pinfunction "PB8_61") (pintype "passive"))
    )
    (net (code "168") (name "unconnected-(U1-PB9-Pad62)") (class "Default")
      (node (ref "U1") (pin "62") (pinfunction "PB9_62") (pintype "passive"))
    )
    (net (code "169") (name "unconnected-(U1-PB10-Pad29)") (class "Default")
      (node (ref "U1") (pin "29") (pinfunction "PB10_29") (pintype "passive"))
    )
    (net (code "170") (name "unconnected-(U1-PB11-Pad30)") (class "Default")
      (node (ref "U1") (pin "30") (pinfunction "PB11_30") (pintype "passive"))
    )
    (net (code "171") (name "unconnected-(U1-PB12-Pad33)") (class "Default")
      (node (ref "U1") (pin "33") (pinfunction "PB12_33") (pintype "passive"))
    )
    (net (code "172") (name "unconnected-(U1-PB13-Pad34)") (class "Default")
      (node (ref "U1") (pin "34") (pinfunction "PB13_34") (pintype "passive"))
    )
    (net (code "173") (name "unconnected-(U1-PB14-Pad35)") (class "Default")
      (node (ref "U1") (pin "35") (pinfunction "PB14_35") (pintype "passive"))
    )
    (net (code "174") (name "unconnected-(U1-PB15-Pad36)") (class "Default")
      (node (ref "U1") (pin "36") (pinfunction "PB15_36") (pintype "passive"))
    )
    (net (code "175") (name "unconnected-(U1-PC0-Pad8)") (class "Default")
      (node (ref "U1") (pin "8") (pinfunction "PC0_8") (pintype "passive"))
    )
    (net (code "176") (name "unconnected-(U1-PC1-Pad9)") (class "Default")
      (node (ref "U1") (pin "9") (pinfunction "PC1_9") (pintype "passive"))
    )
    (net (code "177") (name "unconnected-(U1-PC2-Pad10)") (class "Default")
      (node (ref "U1") (pin "10") (pinfunction "PC2_10") (pintype "passive"))
    )
    (net (code "178") (name "unconnected-(U1-PC3-Pad11)") (class "Default")
      (node (ref "U1") (pin "11") (pinfunction "PC3_11") (pintype "passive"))
    )
    (net (code "179") (name "unconnected-(U1-PC4-Pad24)") (class "Default")
      (node (ref "U1") (pin "24") (pinfunction "PC4_24") (pintype "passive"))
    )
    (net (code "180") (name "unconnected-(U1-PC5-Pad25)") (class "Default")
      (node (ref "U1") (pin "25") (pinfunction "PC5_25") (pintype "passive"))
    )
    (net (code "181") (name "unconnected-(U1-PC6-Pad37)") (class "Default")
      (node (ref "U1") (pin "37") (pinfunction "PC6_37") (pintype "passive"))
    )
    (net (code "182") (name "unconnected-(U1-PC7-Pad38)") (class "Default")
      (node (ref "U1") (pin "38") (pinfunction "PC7_38") (pintype "passive"))
    )
    (net (code "183") (name "unconnected-(U1-PC8-Pad39)") (class "Default")
      (node (ref "U1") (pin "39") (pinfunction "PC8_39") (pintype "passive"))
    )
    (net (code "184") (name "unconnected-(U1-PC9-Pad40)") (class "Default")
      (node (ref "U1") (pin "40") (pinfunction "PC9_40") (pintype "passive"))
    )
    (net (code "185") (name "unconnected-(U1-PC10-Pad51)") (class "Default")
      (node (ref "U1") (pin "51") (pinfunction "PC10_51") (pintype "passive"))
    )
    (net (code "186") (name "unconnected-(U1-PC11-Pad52)") (class "Default")
      (node (ref "U1") (pin "52") (pinfunction "PC11_52") (pintype "passive"))
    )
    (net (code "187") (name "unconnected-(U1-PC12-Pad53)") (class "Default")
      (node (ref "U1") (pin "53") (pinfunction "PC12_53") (pintype "passive"))
    )
    (net (code "188") (name "unconnected-(U1-PC13-Pad2)") (class "Default")
      (node (ref "U1") (pin "2") (pinfunction "PC13_2") (pintype "passive"))
    )
    (net (code "189") (name "unconnected-(U1-PC14-Pad3)") (class "Default")
      (node (ref "U1") (pin "3") (pinfunction "PC14_3") (pintype "passive"))
    )
    (net (code "190") (name "unconnected-(U1-PC15-Pad4)") (class "Default")
      (node (ref "U1") (pin "4") (pinfunction "PC15_4") (pintype "passive"))
    )
    (net (code "191") (name "unconnected-(U1-PD2-Pad54)") (class "Default")
      (node (ref "U1") (pin "54") (pinfunction "PD2_54") (pintype "passive"))
    )
    (net (code "192") (name "unconnected-(U1-PH0-OSC-Pad5)") (class "Default")
      (node (ref "U1") (pin "5") (pinfunction "PH0-OSC_5") (pintype "passive"))
    )
    (net (code "193") (name "unconnected-(U1-PH1-OSC-Pad6)") (class "Default")
      (node (ref "U1") (pin "6") (pinfunction "PH1-OSC_6") (pintype "passive"))
    )
    (net (code "194") (name "unconnected-(U1-VBAT-Pad1)") (class "Default")
      (node (ref "U1") (pin "1") (pinfunction "VBAT_1") (pintype "passive"))
    )
    (net (code "195") (name "unconnected-(U1-VCAP_1-Pad31)") (class "Default")
      (node (ref "U1") (pin "31") (pinfunction "VCAP_1_31") (pintype "passive"))
    )
    (net (code "196") (name "unconnected-(U1-VCAP_2-Pad47)") (class "Default")
      (node (ref "U1") (pin "47") (pinfunction "VCAP_2_47") (pintype "passive"))
    )
    (net (code "197") (name "unconnected-(U1-VDD-Pad19)") (class "Default")
      (node (ref "U1") (pin "19") (pinfunction "VDD_19") (pintype "passive"))
    )
    (net (code "198") (name "unconnected-(U1-VDD-Pad32)") (class "Default")
      (node (ref "U1") (pin "32") (pinfunction "VDD_32") (pintype "passive"))
    )
    (net (code "199") (name "unconnected-(U1-VDD-Pad48)") (class "Default")
      (node (ref "U1") (pin "48") (pinfunction "VDD_48") (pintype "passive"))
    )
    (net (code "200") (name "unconnected-(U1-VDD-Pad64)") (class "Default")
      (node (ref "U1") (pin "64") (pinfunction "VDD_64") (pintype "passive"))
    )
    (net (code "201") (name "unconnected-(U1-VDDA-Pad13)") (class "Default")
      (node (ref "U1") (pin "13") (pinfunction "VDDA_13") (pintype "passive"))
    )
    (net (code "202") (name "unconnected-(U1-VSS-Pad18)") (class "Default")
      (node (ref "U1") (pin "18") (pinfunction "VSS_18") (pintype "passive"))
    )
    (net (code "203") (name "unconnected-(U1-VSS-Pad63)") (class "Default")
      (node (ref "U1") (pin "63") (pinfunction "VSS_63") (pintype "passive"))
    )
    (net (code "204") (name "unconnected-(U1-VSSA-Pad12)") (class "Default")
      (node (ref "U1") (pin "12") (pinfunction "VSSA_12") (pintype "passive"))
    )
    (net (code "205") (name "unconnected-(U2-ACTLED-Pad27)") (class "Default")
      (node (ref "U2") (pin "27") (pinfunction "ACTLED_27") (pintype "passive"))
    )
    (net (code "206") (name "unconnected-(U2-DNC-Pad7)") (class "Default")
      (node (ref "U2") (pin "7") (pinfunction "DNC_7") (pintype "passive"))
    )
    (net (code "207") (name "unconnected-(U2-DUPLED-Pad26)") (class "Default")
      (node (ref "U2") (pin "26") (pinfunction "DUPLED_26") (pintype "passive"))
    )
    (net (code "208") (name "unconnected-(U2-LINKLED-Pad25)") (class "Default")
      (node (ref "U2") (pin "25") (pinfunction "LINKLED_25") (pintype "passive"))
    )
    (net (code "209") (name "unconnected-(U2-NC-Pad12)") (class "Default")
      (node (ref "U2") (pin "12") (pinfunction "NC_12") (pintype "passive"))
    )
    (net (code "210") (name "unconnected-(U2-NC-Pad13)") (class "Default")
      (node (ref "U2") (pin "13") (pinfunction "NC_13") (pintype "passive"))
    )
    (net (code "211") (name "unconnected-(U2-NC-Pad46)") (class "Default")
      (node (ref "U2") (pin "46") (pinfunction "NC_46") (pintype "passive"))
    )
    (net (code "212") (name "unconnected-(U2-NC-Pad47)") (class "Default")
      (node (ref "U2") (pin "47") (pinfunction "NC_47") (pintype "passive"))
    )
    (net (code "213") (name "unconnected-(U2-RSVD-Pad23)") (class "Default")
      (node (ref "U2") (pin "23") (pinfunction "RSVD_23") (pintype "passive"))
    )
    (net (code "214") (name "unconnected-(U2-RSVD-Pad38)") (class "Default")
      (node (ref "U2") (pin "38") (pinfunction "RSVD_38") (pintype "passive"))
    )
    (net (code "215") (name "unconnected-(U2-RSVD-Pad39)") (class "Default")
      (node (ref "U2") (pin "39") (pinfunction "RSVD_39") (pintype "passive"))
    )
    (net (code "216") (name "unconnected-(U2-RSVD-Pad40)") (class "Default")
      (node (ref "U2") (pin "40") (pinfunction "RSVD_40") (pintype "passive"))
    )
    (net (code "217") (name "unconnected-(U2-RSVD-Pad41)") (class "Default")
      (node (ref "U2") (pin "41") (pinfunction "RSVD_41") (pintype "passive"))
    )
    (net (code "218") (name "unconnected-(U2-RSVD-Pad42)") (class "Default")
      (node (ref "U2") (pin "42") (pinfunction "RSVD_42") (pintype "passive"))
    )
    (net (code "219") (name "unconnected-(U2-SPDLED-Pad24)") (class "Default")
      (node (ref "U2") (pin "24") (pinfunction "SPDLED_24") (pintype "passive"))
    )
    (net (code "220") (name "unconnected-(U2-VBG-Pad18)") (class "Default")
      (node (ref "U2") (pin "18") (pinfunction "VBG_18") (pintype "passive"))
    )
    (net (code "221") (name "unconnected-(U2-XO-Pad31)") (class "Default")
      (node (ref "U2") (pin "31") (pinfunction "XO_31") (pintype "passive"))
    )
    (net (code "222") (name "unconnected-(U3-DIR-Pad1)") (class "Default")
      (node (ref "U3") (pin "1") (pinfunction "DIR_1") (pintype "passive"))
    )
    (net (code "223") (name "unconnected-(U3-GND-Pad10)") (class "Default")
      (node (ref "U3") (pin "10") (pinfunction "GND_10") (pintype "passive"))
    )
    (net (code "224") (name "unconnected-(U3-OE-Pad19)") (class "Default")
      (node (ref "U3") (pin "19") (pinfunction "OE_19") (pintype "passive"))
    )
    (net (code "225") (name "unconnected-(U3-VCC-Pad20)") (class "Default")
      (node (ref "U3") (pin "20") (pinfunction "VCC_20") (pintype "passive"))
    )
    (net (code "226") (name "unconnected-(U4-2A4-Pad17)") (class "Default")
      (node (ref "U4") (pin "17") (pinfunction "2A4_17") (pintype "passive"))
    )
    (net (code "227") (name "unconnected-(U4-2Y4-Pad3)") (class "Default")
      (node (ref "U4") (pin "3") (pinfunction "2Y4_3") (pintype "passive"))
    )
    (net (code "228") (name "unconnected-(U4-GND-Pad10)") (class "Default")
      (node (ref "U4") (pin "10") (pinfunction "GND_10") (pintype "passive"))
    )
    (net (code "229") (name "unconnected-(U4-OE1-Pad1)") (class "Default")
      (node (ref "U4") (pin "1") (pinfunction "OE1_1") (pintype "passive"))
    )
    (net (code "230") (name "unconnected-(U4-OE2-Pad19)") (class "Default")
      (node (ref "U4") (pin "19") (pinfunction "OE2_19") (pintype "passive"))
    )
    (net (code "231") (name "unconnected-(U4-VCC-Pad20)") (class "Default")
      (node (ref "U4") (pin "20") (pinfunction "VCC_20") (pintype "passive"))
    )
    (net (code "232") (name "unconnected-(U5-1A1-Pad2)") (class "Default")
      (node (ref "U5") (pin "2") (pinfunction "1A1_2") (pintype "passive"))
    )
    (net (code "233") (name "unconnected-(U5-1A2-Pad4)") (class "Default")
      (node (ref "U5") (pin "4") (pinfunction "1A2_4") (pintype "passive"))
    )
    (net (code "234") (name "unconnected-(U5-1A3-Pad6)") (class "Default")
      (node (ref "U5") (pin "6") (pinfunction "1A3_6") (pintype "passive"))
    )
    (net (code "235") (name "unconnected-(U5-1A4-Pad8)") (class "Default")
      (node (ref "U5") (pin "8") (pinfunction "1A4_8") (pintype "passive"))
    )
    (net (code "236") (name "unconnected-(U5-1Y1-Pad18)") (class "Default")
      (node (ref "U5") (pin "18") (pinfunction "1Y1_18") (pintype "passive"))
    )
    (net (code "237") (name "unconnected-(U5-1Y2-Pad16)") (class "Default")
      (node (ref "U5") (pin "16") (pinfunction "1Y2_16") (pintype "passive"))
    )
    (net (code "238") (name "unconnected-(U5-1Y3-Pad14)") (class "Default")
      (node (ref "U5") (pin "14") (pinfunction "1Y3_14") (pintype "passive"))
    )
    (net (code "239") (name "unconnected-(U5-1Y4-Pad12)") (class "Default")
      (node (ref "U5") (pin "12") (pinfunction "1Y4_12") (pintype "passive"))
    )
    (net (code "240") (name "unconnected-(U5-2A1-Pad11)") (class "Default")
      (node (ref "U5") (pin "11") (pinfunction "2A1_11") (pintype "passive"))
    )
    (net (code "241") (name "unconnected-(U5-2A2-Pad13)") (class "Default")
      (node (ref "U5") (pin "13") (pinfunction "2A2_13") (pintype "passive"))
    )
    (net (code "242") (name "unconnected-(U5-2A3-Pad15)") (class "Default")
      (node (ref "U5") (pin "15") (pinfunction "2A3_15") (pintype "passive"))
    )
    (net (code "243") (name "unconnected-(U5-2A4-Pad17)") (class "Default")
      (node (ref "U5") (pin "17") (pinfunction "2A4_17") (pintype "passive"))
    )
    (net (code "244") (name "unconnected-(U5-2Y1-Pad9)") (class "Default")
      (node (ref "U5") (pin "9") (pinfunction "2Y1_9") (pintype "passive"))
    )
    (net (code "245") (name "unconnected-(U5-2Y2-Pad7)") (class "Default")
      (node (ref "U5") (pin "7") (pinfunction "2Y2_7") (pintype "passive"))
    )
    (net (code "246") (name "unconnected-(U5-2Y3-Pad5)") (class "Default")
      (node (ref "U5") (pin "5") (pinfunction "2Y3_5") (pintype "passive"))
    )
    (net (code "247") (name "unconnected-(U5-2Y4-Pad3)") (class "Default")
      (node (ref "U5") (pin "3") (pinfunction "2Y4_3") (pintype "passive"))
    )
    (net (code "248") (name "unconnected-(U5-GND-Pad10)") (class "Default")
      (node (ref "U5") (pin "10") (pinfunction "GND_10") (pintype "passive"))
    )
    (net (code "249") (name "unconnected-(U5-OE1-Pad1)") (class "Default")
      (node (ref "U5") (pin "1") (pinfunction "OE1_1") (pintype "passive"))
    )
    (net (code "250") (name "unconnected-(U5-OE2-Pad19)") (class "Default")
      (node (ref "U5") (pin "19") (pinfunction "OE2_19") (pintype "passive"))
    )
    (net (code "251") (name "unconnected-(U5-VCC-Pad20)") (class "Default")
      (node (ref "U5") (pin "20") (pinfunction "VCC_20") (pintype "passive"))
    )
  )
)
